# SCH_Control_2024-03-24.net
KiCad netlist of a schematic drawn in EasyEDA
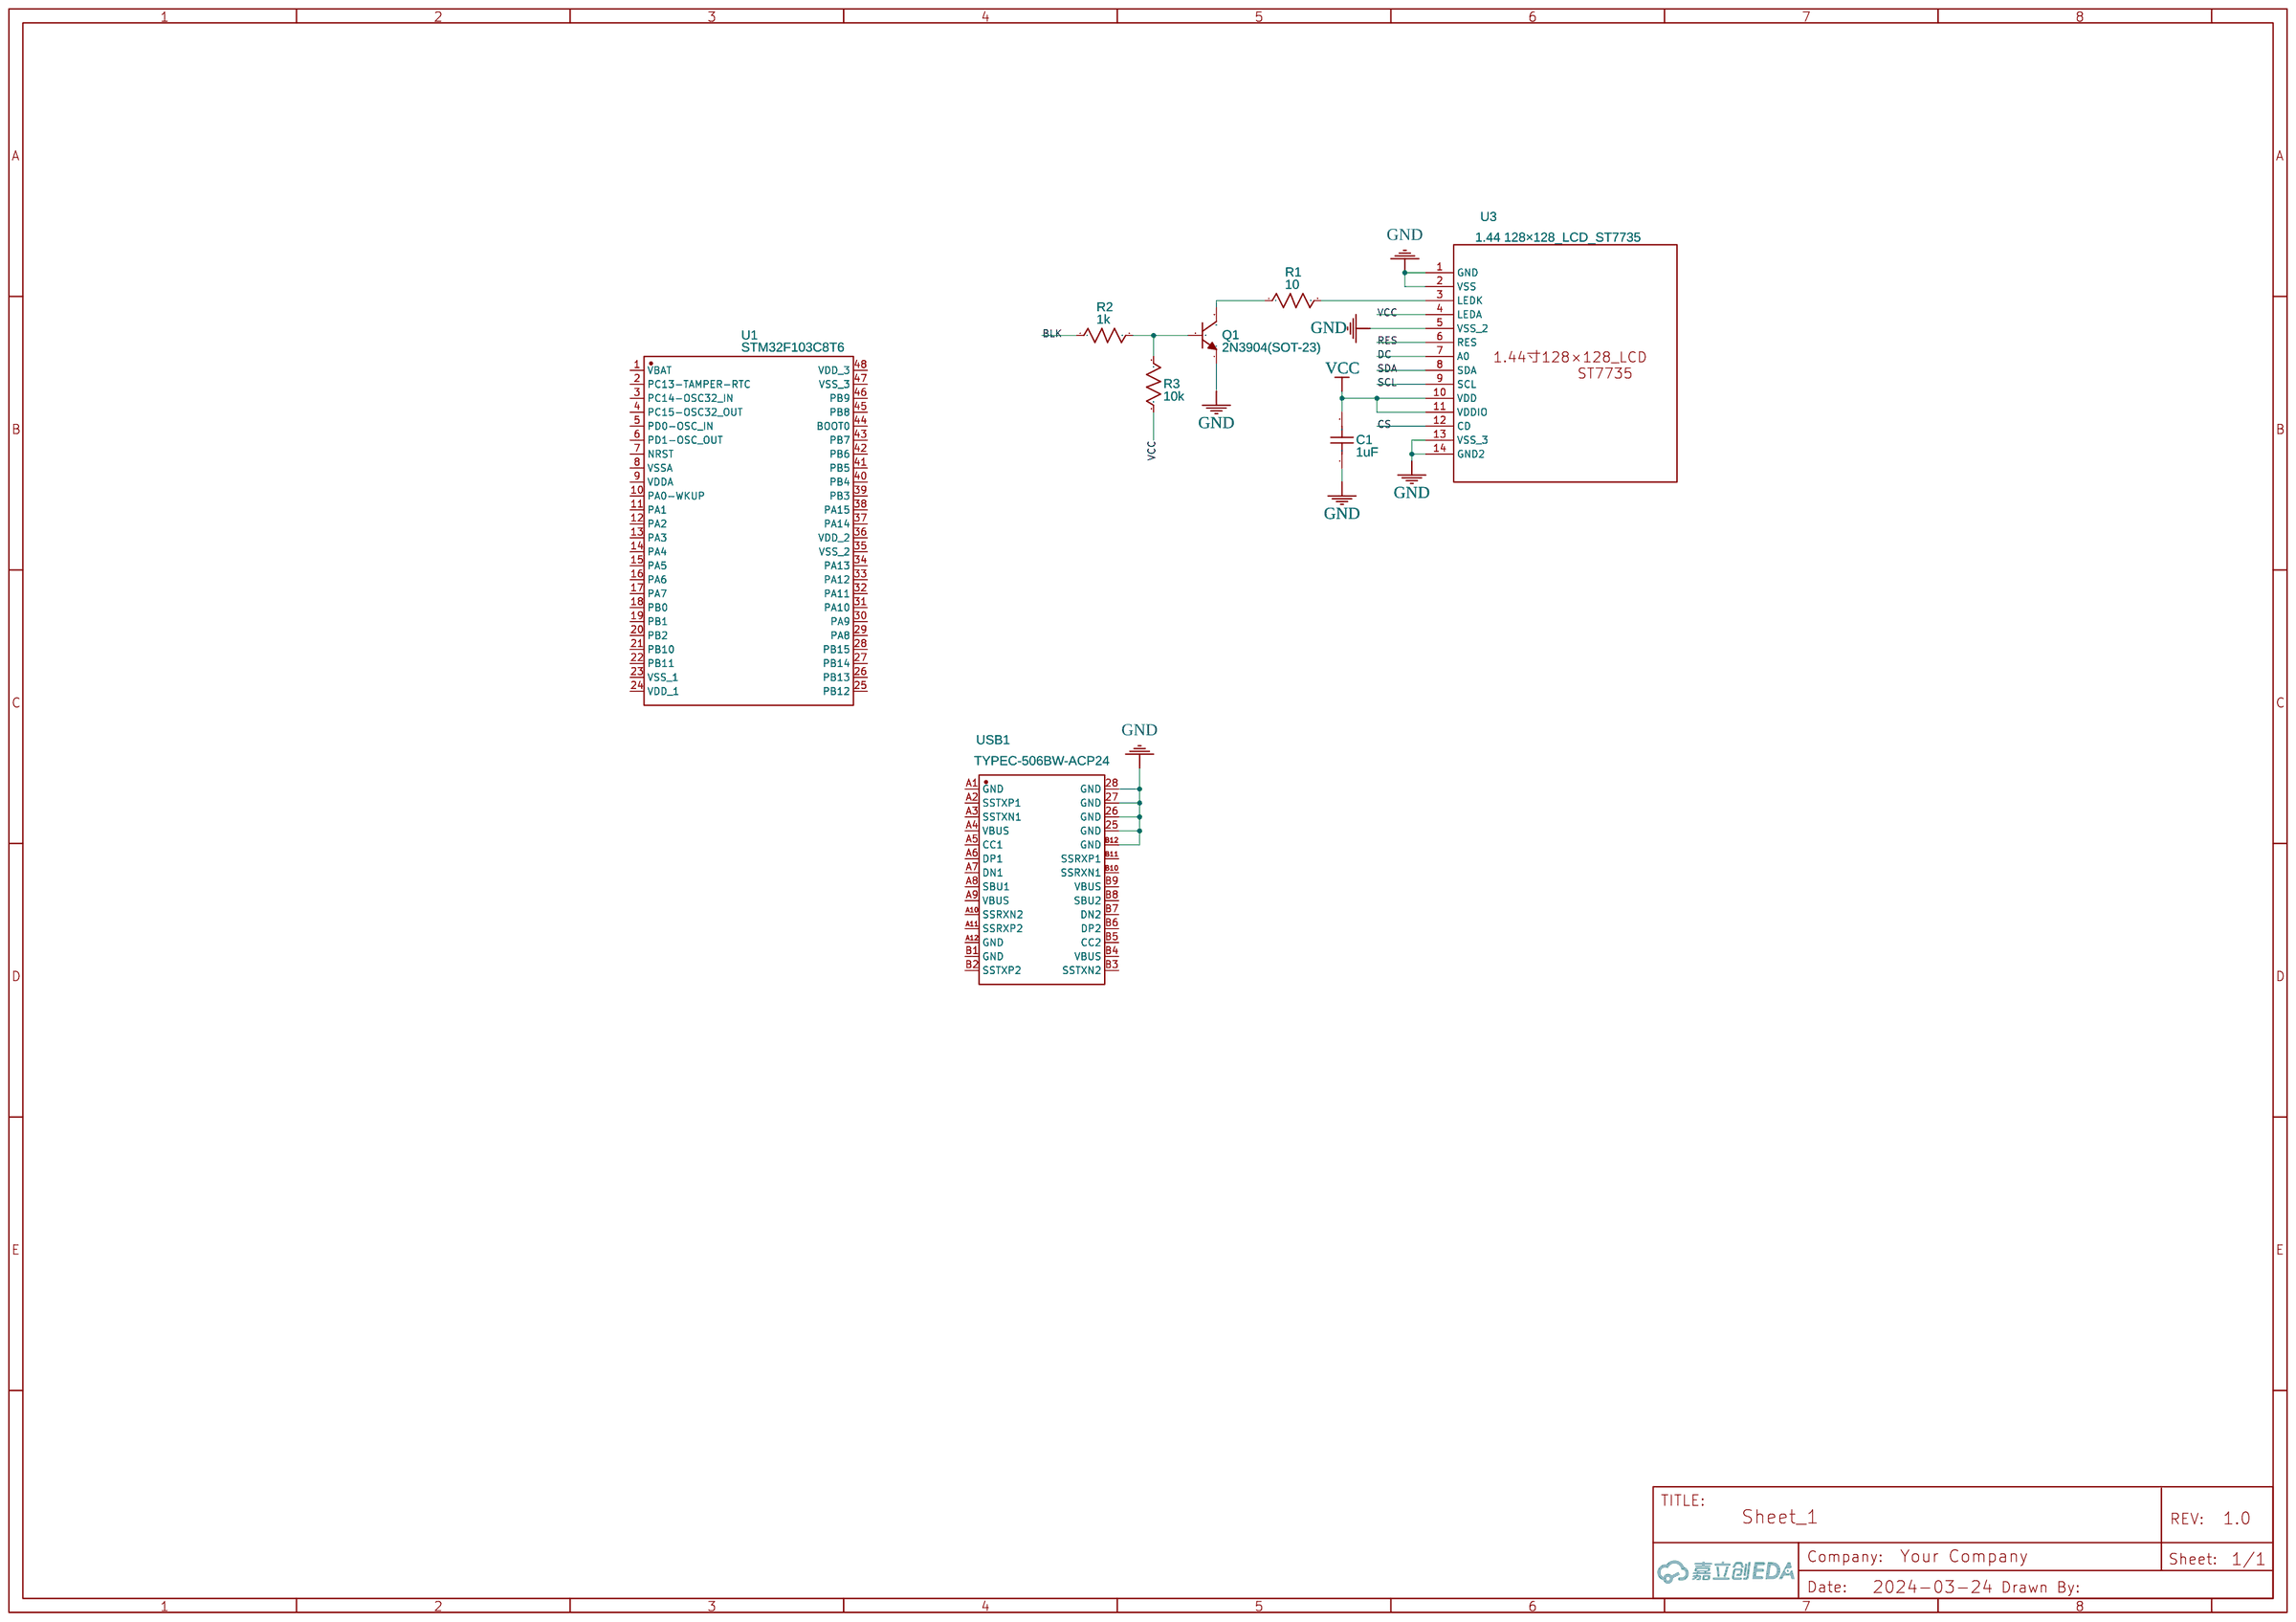
[diagram p0: schematic sheet]

(export (version "E")
  (design (tool "Eeschema 10.0.6"))
  (components
    (comp (ref "C1") (value "1uF") (libsource (lib "") (part "C_0603_US")))
    (comp (ref "Q1")
      (value "2N3904(SOT-23)")
      (fields (field (name "Manufacturer Part") "2n3904S-RTK/PS") (field (name "Manufacturer") "KEC"))
      (libsource (lib "") (part "2N3904(SOT-23)"))
    )
    (comp (ref "R1") (value "10") (libsource (lib "") (part "R_0603_US")))
    (comp (ref "R2") (value "1k") (libsource (lib "") (part "R_0603_US")))
    (comp (ref "R3") (value "10k") (libsource (lib "") (part "R_0603_US_1")))
    (comp (ref "U1")
      (value "STM32F103C8T6")
      (fields (field (name "Manufacturer") "ST(意法半导体)"))
      (libsource (lib "") (part "STM32F103C8T6"))
    )
    (comp (ref "U3")
      (value "1.44 128×128_LCD_ST7735")
      (libsource (lib "") (part "1.44 128×128_LCD_ST7735【华迪短】"))
    )
    (comp (ref "USB1")
      (value "TYPEC-506BW-ACP24")
      (fields (field (name "Manufacturer") "XUNPU(讯普)"))
      (libsource (lib "") (part "TYPEC-506BW-ACP24"))
    )
  )
  (nets
    (net (code "1") (name "/BLK") (class "Default")
      (node (ref "R2") (pin "1") (pinfunction "1_1") (pintype "unspecified"))
    )
    (net (code "2") (name "/CS") (class "Default")
      (node (ref "U3") (pin "12") (pinfunction "CD_12") (pintype "unspecified"))
    )
    (net (code "3") (name "/DC") (class "Default")
      (node (ref "U3") (pin "7") (pinfunction "A0_7") (pintype "unspecified"))
    )
    (net (code "4") (name "/RES") (class "Default")
      (node (ref "U3") (pin "6") (pinfunction "RES_6") (pintype "unspecified"))
    )
    (net (code "5") (name "/SCL") (class "Default")
      (node (ref "U3") (pin "9") (pinfunction "SCL_9") (pintype "unspecified"))
    )
    (net (code "6") (name "/SDA") (class "Default")
      (node (ref "U3") (pin "8") (pinfunction "SDA_8") (pintype "unspecified"))
    )
    (net (code "7") (name "GND") (class "Default")
      (node (ref "C1") (pin "1") (pinfunction "1_1") (pintype "unspecified"))
      (node (ref "Q1") (pin "1") (pinfunction "E_1") (pintype "input"))
      (node (ref "U3") (pin "1") (pinfunction "GND_1") (pintype "unspecified"))
      (node (ref "U3") (pin "13") (pinfunction "VSS_3_13") (pintype "unspecified"))
      (node (ref "U3") (pin "14") (pinfunction "GND2_14") (pintype "unspecified"))
      (node (ref "U3") (pin "2") (pinfunction "VSS_2") (pintype "unspecified"))
      (node (ref "U3") (pin "5") (pinfunction "VSS_2_5") (pintype "unspecified"))
      (node (ref "USB1") (pin "25") (pinfunction "GND_25") (pintype "unspecified"))
      (node (ref "USB1") (pin "26") (pinfunction "GND_26") (pintype "unspecified"))
      (node (ref "USB1") (pin "27") (pinfunction "GND_27") (pintype "unspecified"))
      (node (ref "USB1") (pin "28") (pinfunction "GND_28") (pintype "unspecified"))
      (node (ref "USB1") (pin "B12") (pinfunction "GND_B12") (pintype "unspecified"))
    )
    (net (code "8") (name "Net-(Q1-B)") (class "Default")
      (node (ref "Q1") (pin "2") (pinfunction "B_2") (pintype "input"))
      (node (ref "R2") (pin "2") (pinfunction "2_2") (pintype "unspecified"))
      (node (ref "R3") (pin "2") (pinfunction "2_2") (pintype "unspecified"))
    )
    (net (code "9") (name "Net-(Q1-C)") (class "Default")
      (node (ref "Q1") (pin "3") (pinfunction "C_3") (pintype "input"))
      (node (ref "R1") (pin "1") (pinfunction "1_1") (pintype "unspecified"))
    )
    (net (code "10") (name "Net-(U3-LEDK)") (class "Default")
      (node (ref "R1") (pin "2") (pinfunction "2_2") (pintype "unspecified"))
      (node (ref "U3") (pin "3") (pinfunction "LEDK_3") (pintype "unspecified"))
    )
    (net (code "11") (name "VCC") (class "Default")
      (node (ref "C1") (pin "2") (pinfunction "2_2") (pintype "unspecified"))
      (node (ref "R3") (pin "1") (pinfunction "1_1") (pintype "unspecified"))
      (node (ref "U3") (pin "10") (pinfunction "VDD_10") (pintype "unspecified"))
      (node (ref "U3") (pin "11") (pinfunction "VDDIO_11") (pintype "unspecified"))
      (node (ref "U3") (pin "4") (pinfunction "LEDA_4") (pintype "unspecified"))
    )
    (net (code "12") (name "unconnected-(U1-BOOT0-Pad44)") (class "Default")
      (node (ref "U1") (pin "44") (pinfunction "BOOT0_44") (pintype "unspecified"))
    )
    (net (code "13") (name "unconnected-(U1-NRST-Pad7)") (class "Default")
      (node (ref "U1") (pin "7") (pinfunction "NRST_7") (pintype "unspecified"))
    )
    (net (code "14") (name "unconnected-(U1-PA0-WKUP-Pad10)") (class "Default")
      (node (ref "U1") (pin "10") (pinfunction "PA0-WKUP_10") (pintype "unspecified"))
    )
    (net (code "15") (name "unconnected-(U1-PA1-Pad11)") (class "Default")
      (node (ref "U1") (pin "11") (pinfunction "PA1_11") (pintype "unspecified"))
    )
    (net (code "16") (name "unconnected-(U1-PA2-Pad12)") (class "Default")
      (node (ref "U1") (pin "12") (pinfunction "PA2_12") (pintype "unspecified"))
    )
    (net (code "17") (name "unconnected-(U1-PA3-Pad13)") (class "Default")
      (node (ref "U1") (pin "13") (pinfunction "PA3_13") (pintype "unspecified"))
    )
    (net (code "18") (name "unconnected-(U1-PA4-Pad14)") (class "Default")
      (node (ref "U1") (pin "14") (pinfunction "PA4_14") (pintype "unspecified"))
    )
    (net (code "19") (name "unconnected-(U1-PA5-Pad15)") (class "Default")
      (node (ref "U1") (pin "15") (pinfunction "PA5_15") (pintype "unspecified"))
    )
    (net (code "20") (name "unconnected-(U1-PA6-Pad16)") (class "Default")
      (node (ref "U1") (pin "16") (pinfunction "PA6_16") (pintype "unspecified"))
    )
    (net (code "21") (name "unconnected-(U1-PA7-Pad17)") (class "Default")
      (node (ref "U1") (pin "17") (pinfunction "PA7_17") (pintype "unspecified"))
    )
    (net (code "22") (name "unconnected-(U1-PA8-Pad29)") (class "Default")
      (node (ref "U1") (pin "29") (pinfunction "PA8_29") (pintype "unspecified"))
    )
    (net (code "23") (name "unconnected-(U1-PA9-Pad30)") (class "Default")
      (node (ref "U1") (pin "30") (pinfunction "PA9_30") (pintype "unspecified"))
    )
    (net (code "24") (name "unconnected-(U1-PA10-Pad31)") (class "Default")
      (node (ref "U1") (pin "31") (pinfunction "PA10_31") (pintype "unspecified"))
    )
    (net (code "25") (name "unconnected-(U1-PA11-Pad32)") (class "Default")
      (node (ref "U1") (pin "32") (pinfunction "PA11_32") (pintype "unspecified"))
    )
    (net (code "26") (name "unconnected-(U1-PA12-Pad33)") (class "Default")
      (node (ref "U1") (pin "33") (pinfunction "PA12_33") (pintype "unspecified"))
    )
    (net (code "27") (name "unconnected-(U1-PA13-Pad34)") (class "Default")
      (node (ref "U1") (pin "34") (pinfunction "PA13_34") (pintype "unspecified"))
    )
    (net (code "28") (name "unconnected-(U1-PA14-Pad37)") (class "Default")
      (node (ref "U1") (pin "37") (pinfunction "PA14_37") (pintype "unspecified"))
    )
    (net (code "29") (name "unconnected-(U1-PA15-Pad38)") (class "Default")
      (node (ref "U1") (pin "38") (pinfunction "PA15_38") (pintype "unspecified"))
    )
    (net (code "30") (name "unconnected-(U1-PB0-Pad18)") (class "Default")
      (node (ref "U1") (pin "18") (pinfunction "PB0_18") (pintype "unspecified"))
    )
    (net (code "31") (name "unconnected-(U1-PB1-Pad19)") (class "Default")
      (node (ref "U1") (pin "19") (pinfunction "PB1_19") (pintype "unspecified"))
    )
    (net (code "32") (name "unconnected-(U1-PB2-Pad20)") (class "Default")
      (node (ref "U1") (pin "20") (pinfunction "PB2_20") (pintype "unspecified"))
    )
    (net (code "33") (name "unconnected-(U1-PB3-Pad39)") (class "Default")
      (node (ref "U1") (pin "39") (pinfunction "PB3_39") (pintype "unspecified"))
    )
    (net (code "34") (name "unconnected-(U1-PB4-Pad40)") (class "Default")
      (node (ref "U1") (pin "40") (pinfunction "PB4_40") (pintype "unspecified"))
    )
    (net (code "35") (name "unconnected-(U1-PB5-Pad41)") (class "Default")
      (node (ref "U1") (pin "41") (pinfunction "PB5_41") (pintype "unspecified"))
    )
    (net (code "36") (name "unconnected-(U1-PB6-Pad42)") (class "Default")
      (node (ref "U1") (pin "42") (pinfunction "PB6_42") (pintype "unspecified"))
    )
    (net (code "37") (name "unconnected-(U1-PB7-Pad43)") (class "Default")
      (node (ref "U1") (pin "43") (pinfunction "PB7_43") (pintype "unspecified"))
    )
    (net (code "38") (name "unconnected-(U1-PB8-Pad45)") (class "Default")
      (node (ref "U1") (pin "45") (pinfunction "PB8_45") (pintype "unspecified"))
    )
    (net (code "39") (name "unconnected-(U1-PB9-Pad46)") (class "Default")
      (node (ref "U1") (pin "46") (pinfunction "PB9_46") (pintype "unspecified"))
    )
    (net (code "40") (name "unconnected-(U1-PB10-Pad21)") (class "Default")
      (node (ref "U1") (pin "21") (pinfunction "PB10_21") (pintype "unspecified"))
    )
    (net (code "41") (name "unconnected-(U1-PB11-Pad22)") (class "Default")
      (node (ref "U1") (pin "22") (pinfunction "PB11_22") (pintype "unspecified"))
    )
    (net (code "42") (name "unconnected-(U1-PB12-Pad25)") (class "Default")
      (node (ref "U1") (pin "25") (pinfunction "PB12_25") (pintype "unspecified"))
    )
    (net (code "43") (name "unconnected-(U1-PB13-Pad26)") (class "Default")
      (node (ref "U1") (pin "26") (pinfunction "PB13_26") (pintype "unspecified"))
    )
    (net (code "44") (name "unconnected-(U1-PB14-Pad27)") (class "Default")
      (node (ref "U1") (pin "27") (pinfunction "PB14_27") (pintype "unspecified"))
    )
    (net (code "45") (name "unconnected-(U1-PB15-Pad28)") (class "Default")
      (node (ref "U1") (pin "28") (pinfunction "PB15_28") (pintype "unspecified"))
    )
    (net (code "46") (name "unconnected-(U1-PC13-TAMPER-RTC-Pad2)") (class "Default")
      (node (ref "U1") (pin "2") (pinfunction "PC13-TAMPER-RTC_2") (pintype "unspecified"))
    )
    (net (code "47") (name "unconnected-(U1-PC14-OSC32_IN-Pad3)") (class "Default")
      (node (ref "U1") (pin "3") (pinfunction "PC14-OSC32_IN_3") (pintype "unspecified"))
    )
    (net (code "48") (name "unconnected-(U1-PC15-OSC32_OUT-Pad4)") (class "Default")
      (node (ref "U1") (pin "4") (pinfunction "PC15-OSC32_OUT_4") (pintype "unspecified"))
    )
    (net (code "49") (name "unconnected-(U1-PD0-OSC_IN-Pad5)") (class "Default")
      (node (ref "U1") (pin "5") (pinfunction "PD0-OSC_IN_5") (pintype "unspecified"))
    )
    (net (code "50") (name "unconnected-(U1-PD1-OSC_OUT-Pad6)") (class "Default")
      (node (ref "U1") (pin "6") (pinfunction "PD1-OSC_OUT_6") (pintype "unspecified"))
    )
    (net (code "51") (name "unconnected-(U1-VBAT-Pad1)") (class "Default")
      (node (ref "U1") (pin "1") (pinfunction "VBAT_1") (pintype "unspecified"))
    )
    (net (code "52") (name "unconnected-(U1-VDDA-Pad9)") (class "Default")
      (node (ref "U1") (pin "9") (pinfunction "VDDA_9") (pintype "unspecified"))
    )
    (net (code "53") (name "unconnected-(U1-VDD_1-Pad24)") (class "Default")
      (node (ref "U1") (pin "24") (pinfunction "VDD_1_24") (pintype "unspecified"))
    )
    (net (code "54") (name "unconnected-(U1-VDD_2-Pad36)") (class "Default")
      (node (ref "U1") (pin "36") (pinfunction "VDD_2_36") (pintype "unspecified"))
    )
    (net (code "55") (name "unconnected-(U1-VDD_3-Pad48)") (class "Default")
      (node (ref "U1") (pin "48") (pinfunction "VDD_3_48") (pintype "unspecified"))
    )
    (net (code "56") (name "unconnected-(U1-VSSA-Pad8)") (class "Default")
      (node (ref "U1") (pin "8") (pinfunction "VSSA_8") (pintype "unspecified"))
    )
    (net (code "57") (name "unconnected-(U1-VSS_1-Pad23)") (class "Default")
      (node (ref "U1") (pin "23") (pinfunction "VSS_1_23") (pintype "unspecified"))
    )
    (net (code "58") (name "unconnected-(U1-VSS_2-Pad35)") (class "Default")
      (node (ref "U1") (pin "35") (pinfunction "VSS_2_35") (pintype "unspecified"))
    )
    (net (code "59") (name "unconnected-(U1-VSS_3-Pad47)") (class "Default")
      (node (ref "U1") (pin "47") (pinfunction "VSS_3_47") (pintype "unspecified"))
    )
    (net (code "60") (name "unconnected-(USB1-CC1-PadA5)") (class "Default")
      (node (ref "USB1") (pin "A5") (pinfunction "CC1_A5") (pintype "unspecified"))
    )
    (net (code "61") (name "unconnected-(USB1-CC2-PadB5)") (class "Default")
      (node (ref "USB1") (pin "B5") (pinfunction "CC2_B5") (pintype "unspecified"))
    )
    (net (code "62") (name "unconnected-(USB1-DN1-PadA7)") (class "Default")
      (node (ref "USB1") (pin "A7") (pinfunction "DN1_A7") (pintype "unspecified"))
    )
    (net (code "63") (name "unconnected-(USB1-DN2-PadB7)") (class "Default")
      (node (ref "USB1") (pin "B7") (pinfunction "DN2_B7") (pintype "unspecified"))
    )
    (net (code "64") (name "unconnected-(USB1-DP1-PadA6)") (class "Default")
      (node (ref "USB1") (pin "A6") (pinfunction "DP1_A6") (pintype "unspecified"))
    )
    (net (code "65") (name "unconnected-(USB1-DP2-PadB6)") (class "Default")
      (node (ref "USB1") (pin "B6") (pinfunction "DP2_B6") (pintype "unspecified"))
    )
    (net (code "66") (name "unconnected-(USB1-GND-PadA1)") (class "Default")
      (node (ref "USB1") (pin "A1") (pinfunction "GND_A1") (pintype "unspecified"))
    )
    (net (code "67") (name "unconnected-(USB1-GND-PadA12)") (class "Default")
      (node (ref "USB1") (pin "A12") (pinfunction "GND_A12") (pintype "unspecified"))
    )
    (net (code "68") (name "unconnected-(USB1-GND-PadB1)") (class "Default")
      (node (ref "USB1") (pin "B1") (pinfunction "GND_B1") (pintype "unspecified"))
    )
    (net (code "69") (name "unconnected-(USB1-SBU1-PadA8)") (class "Default")
      (node (ref "USB1") (pin "A8") (pinfunction "SBU1_A8") (pintype "unspecified"))
    )
    (net (code "70") (name "unconnected-(USB1-SBU2-PadB8)") (class "Default")
      (node (ref "USB1") (pin "B8") (pinfunction "SBU2_B8") (pintype "unspecified"))
    )
    (net (code "71") (name "unconnected-(USB1-SSRXN1-PadB10)") (class "Default")
      (node (ref "USB1") (pin "B10") (pinfunction "SSRXN1_B10") (pintype "unspecified"))
    )
    (net (code "72") (name "unconnected-(USB1-SSRXN2-PadA10)") (class "Default")
      (node (ref "USB1") (pin "A10") (pinfunction "SSRXN2_A10") (pintype "unspecified"))
    )
    (net (code "73") (name "unconnected-(USB1-SSRXP1-PadB11)") (class "Default")
      (node (ref "USB1") (pin "B11") (pinfunction "SSRXP1_B11") (pintype "unspecified"))
    )
    (net (code "74") (name "unconnected-(USB1-SSRXP2-PadA11)") (class "Default")
      (node (ref "USB1") (pin "A11") (pinfunction "SSRXP2_A11") (pintype "unspecified"))
    )
    (net (code "75") (name "unconnected-(USB1-SSTXN1-PadA3)") (class "Default")
      (node (ref "USB1") (pin "A3") (pinfunction "SSTXN1_A3") (pintype "unspecified"))
    )
    (net (code "76") (name "unconnected-(USB1-SSTXN2-PadB3)") (class "Default")
      (node (ref "USB1") (pin "B3") (pinfunction "SSTXN2_B3") (pintype "unspecified"))
    )
    (net (code "77") (name "unconnected-(USB1-SSTXP1-PadA2)") (class "Default")
      (node (ref "USB1") (pin "A2") (pinfunction "SSTXP1_A2") (pintype "unspecified"))
    )
    (net (code "78") (name "unconnected-(USB1-SSTXP2-PadB2)") (class "Default")
      (node (ref "USB1") (pin "B2") (pinfunction "SSTXP2_B2") (pintype "unspecified"))
    )
    (net (code "79") (name "unconnected-(USB1-VBUS-PadA4)") (class "Default")
      (node (ref "USB1") (pin "A4") (pinfunction "VBUS_A4") (pintype "unspecified"))
    )
    (net (code "80") (name "unconnected-(USB1-VBUS-PadA9)") (class "Default")
      (node (ref "USB1") (pin "A9") (pinfunction "VBUS_A9") (pintype "unspecified"))
    )
    (net (code "81") (name "unconnected-(USB1-VBUS-PadB4)") (class "Default")
      (node (ref "USB1") (pin "B4") (pinfunction "VBUS_B4") (pintype "unspecified"))
    )
    (net (code "82") (name "unconnected-(USB1-VBUS-PadB9)") (class "Default")
      (node (ref "USB1") (pin "B9") (pinfunction "VBUS_B9") (pintype "unspecified"))
    )
  )
)
